# RELAY20.net
KiCad netlist of a schematic drawn in Altium Designer
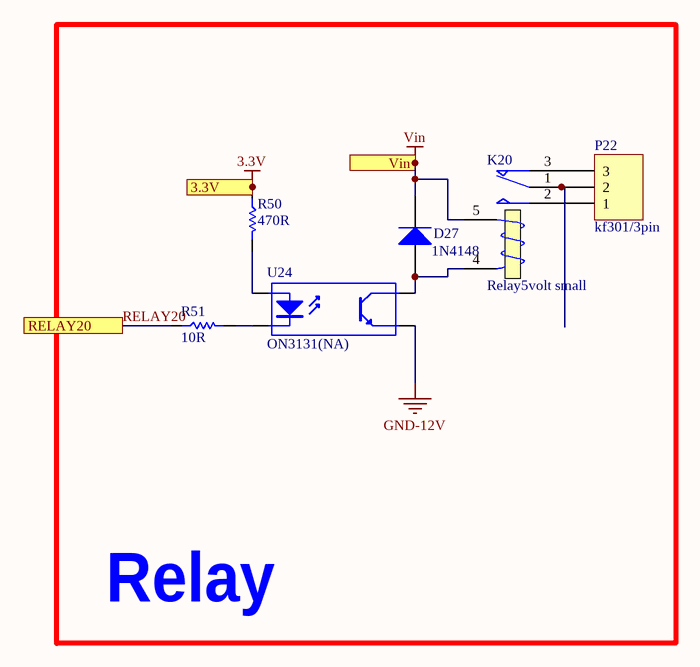
[diagram p0: RELAY20.SchDoc]

(export (version "E")
  (design (tool "Eeschema 10.0.6"))
  (components
    (comp (ref "D27")
      (value "1N4148")
      (footprint "sod123")
      (description "1 Amp General Purpose Rectifier")
      (fields (field (name "PUBLISHER") "Altium Limited"))
      (libsource (lib "Miscellaneous Devices") (part "Diode 1N4007"))
    )
    (comp (ref "K20")
      (value "Relay5volt small")
      (footprint "relay5_childern")
      (description "SPDT Relay")
      (fields (field (name "PUBLISHER") "Altium Limited"))
      (libsource (lib "FLIB") (part "Relay"))
    )
    (comp (ref "P22")
      (value "kf301/3pin")
      (footprint "Blue Connector 1*3 -kf301")
      (fields (field (name "PUBLISHER") "Altium Limited"))
      (libsource (lib "Miscellaneous Connectors") (part "Header 3"))
    )
    (comp (ref "R50")
      (value "470R")
      (footprint "0805/resistor")
      (description "Resistor")
      (fields (field (name "TOLERANCE") "5%") (field (name "POWER") "1/8 W"))
      (libsource (lib "skille") (part "Resistor"))
    )
    (comp (ref "R51")
      (value "10R")
      (footprint "0805/resistor")
      (description "Resistor")
      (fields (field (name "TOLERANCE") "5%") (field (name "POWER") "1/8 W"))
      (libsource (lib "skille") (part "Resistor"))
    )
    (comp (ref "U24")
      (value "ON3131(NA)")
      (footprint "OPTO_COUPLER")
      (description "4-Pin Phototransistor Optocoupler")
      (fields (field (name "PUBLISHER") "Altium Limited"))
      (libsource (lib "skille") (part "Optoisolator1"))
    )
  )
  (nets
    (net (code "1") (name "/RELAY20") (class "Default")
      (node (ref "R51") (pin "1") (pinfunction "1_1") (pintype "passive"))
    )
    (net (code "2") (name "3.3V") (class "Default")
      (node (ref "R50") (pin "1") (pinfunction "1_1") (pintype "passive"))
    )
    (net (code "3") (name "GND-12V") (class "Default")
      (node (ref "U24") (pin "3") (pinfunction "E_3") (pintype "passive"))
    )
    (net (code "4") (name "Net-(K20-COM)") (class "Default")
      (node (ref "K20") (pin "1") (pinfunction "COM_1") (pintype "passive"))
      (node (ref "P22") (pin "2") (pinfunction "2_2") (pintype "passive"))
    )
    (net (code "5") (name "Net-(K20-NO)") (class "Default")
      (node (ref "K20") (pin "2") (pinfunction "NO_2") (pintype "passive"))
      (node (ref "P22") (pin "1") (pinfunction "1_1") (pintype "passive"))
    )
    (net (code "6") (name "Net-(K20-T1)") (class "Default")
      (node (ref "K20") (pin "3") (pinfunction "T1_3") (pintype "passive"))
      (node (ref "P22") (pin "3") (pinfunction "3_3") (pintype "passive"))
    )
    (net (code "7") (name "Net-(K20-T2)") (class "Default")
      (node (ref "D27") (pin "A") (pinfunction "A_A") (pintype "passive"))
      (node (ref "K20") (pin "4") (pinfunction "T2_4") (pintype "passive"))
      (node (ref "U24") (pin "4") (pinfunction "C_4") (pintype "passive"))
    )
    (net (code "8") (name "Net-(U24-A)") (class "Default")
      (node (ref "R50") (pin "2") (pinfunction "2_2") (pintype "passive"))
      (node (ref "U24") (pin "1") (pinfunction "A_1") (pintype "passive"))
    )
    (net (code "9") (name "Net-(U24-K)") (class "Default")
      (node (ref "R51") (pin "2") (pinfunction "2_2") (pintype "passive"))
      (node (ref "U24") (pin "2") (pinfunction "K_2") (pintype "passive"))
    )
    (net (code "10") (name "Vin") (class "Default")
      (node (ref "D27") (pin "K") (pinfunction "K_K") (pintype "passive"))
      (node (ref "K20") (pin "5") (pinfunction "5_5") (pintype "passive"))
    )
  )
)
